# Current_Measurement.net
KiCad netlist of a schematic drawn in Altium Designer
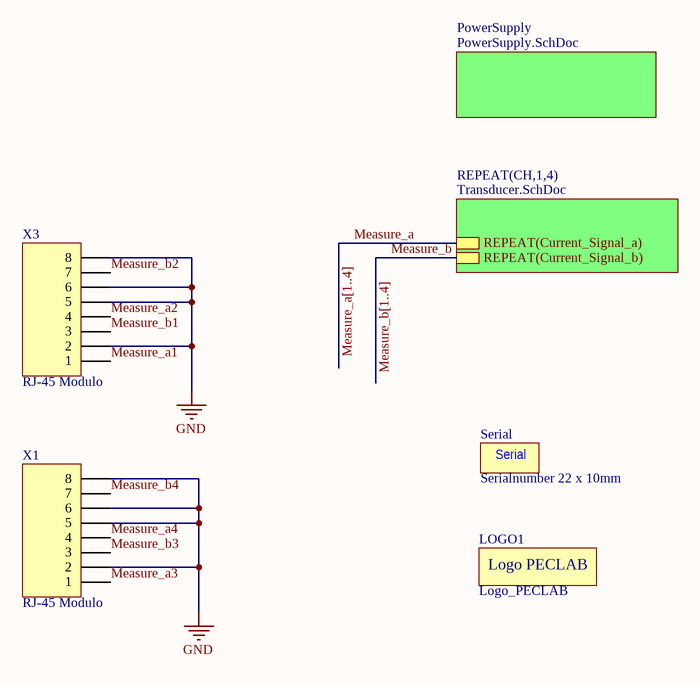
[diagram p0: Current Measurement.SchDoc]

(export (version "E")
  (design (tool "Eeschema 10.0.6"))
  (components
    (comp (ref "LOGO1")
      (value "Logo_PECLAB")
      (footprint "Logo_PECLAB")
      (libsource (lib "Current_SCH_Libraries") (part "Logo_PECLAB"))
    )
    (comp (ref "Serial")
      (value "Serialnumber 22 x 10mm")
      (footprint "Serial_22x10mm")
      (fields (field (name "CREATED") "2020_07_12_DArancibia"))
      (libsource (lib "Current_SCH_Libraries") (part "SerialNumber"))
    )
    (comp (ref "X1")
      (value "RJ-45 Modulo")
      (footprint "RJ45_RJHSE5E80")
      (description "Modulo RJ-45 RJHSE5E80")
      (fields
        (field (name "MANUFACTURER") "Amphenol Commercial")
        (field (name "MANUFACTURER PART NUMBER") "RJHSE5E80")
        (field (name "PUBLISHER") "Altium Limited")
      )
      (libsource (lib "Current_SCH_Libraries") (part "RJ45_RJHSE5E80"))
    )
    (comp (ref "X3")
      (value "RJ-45 Modulo")
      (footprint "RJ45_RJHSE5E80")
      (description "Modulo RJ-45 RJHSE5E80")
      (fields
        (field (name "MANUFACTURER") "Amphenol Commercial")
        (field (name "MANUFACTURER PART NUMBER") "RJHSE5E80")
        (field (name "PUBLISHER") "Altium Limited")
      )
      (libsource (lib "Current_SCH_Libraries") (part "RJ45_RJHSE5E80"))
    )
  )
  (nets
    (net (code "2") (name "/Measure_a1") (class "Default")
      (node (ref "X3") (pin "1") (pinfunction "1_1") (pintype "passive"))
    )
    (net (code "3") (name "/Measure_a2") (class "Default")
      (node (ref "X3") (pin "4") (pinfunction "4_4") (pintype "passive"))
    )
    (net (code "4") (name "/Measure_a3") (class "Default")
      (node (ref "X1") (pin "1") (pinfunction "1_1") (pintype "passive"))
    )
    (net (code "5") (name "/Measure_a4") (class "Default")
      (node (ref "X1") (pin "4") (pinfunction "4_4") (pintype "passive"))
    )
    (net (code "8") (name "/Measure_b1") (class "Default")
      (node (ref "X3") (pin "3") (pinfunction "3_3") (pintype "passive"))
    )
    (net (code "9") (name "/Measure_b2") (class "Default")
      (node (ref "X3") (pin "7") (pinfunction "7_7") (pintype "passive"))
    )
    (net (code "10") (name "/Measure_b3") (class "Default")
      (node (ref "X1") (pin "3") (pinfunction "3_3") (pintype "passive"))
    )
    (net (code "11") (name "/Measure_b4") (class "Default")
      (node (ref "X1") (pin "7") (pinfunction "7_7") (pintype "passive"))
    )
    (net (code "13") (name "GND") (class "Default")
      (node (ref "X1") (pin "2") (pinfunction "2_2") (pintype "passive"))
      (node (ref "X1") (pin "5") (pinfunction "5_5") (pintype "passive"))
      (node (ref "X1") (pin "6") (pinfunction "6_6") (pintype "passive"))
      (node (ref "X1") (pin "8") (pinfunction "8_8") (pintype "passive"))
      (node (ref "X3") (pin "2") (pinfunction "2_2") (pintype "passive"))
      (node (ref "X3") (pin "5") (pinfunction "5_5") (pintype "passive"))
      (node (ref "X3") (pin "6") (pinfunction "6_6") (pintype "passive"))
      (node (ref "X3") (pin "8") (pinfunction "8_8") (pintype "passive"))
    )
  )
)
